# Sheet1.net
KiCad netlist of a schematic drawn in Altium Designer
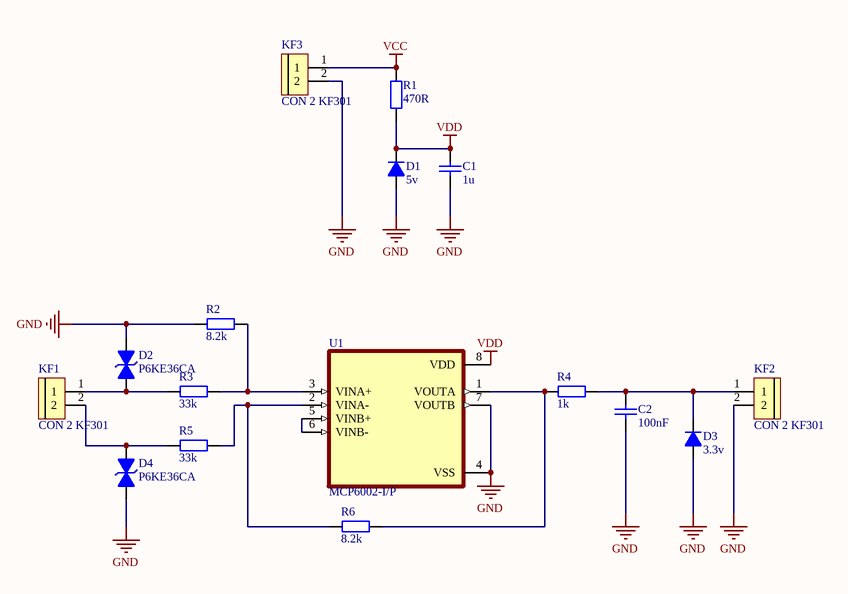
[diagram p0: Sheet1.SchDoc]

(export (version "E")
  (design (tool "Eeschema 10.0.6"))
  (components
    (comp (ref "C1")
      (value "1u")
      (footprint "tu gom")
      (description "Cắm")
      (libsource (lib "Altium_Lib_by_KhueNguyenCreator") (part "Tu gom 15pF 50V"))
    )
    (comp (ref "C2")
      (value "100nF")
      (footprint "tu gom")
      (description "Cắm")
      (libsource (lib "Altium_Lib_by_KhueNguyenCreator") (part "Tu gom 15pF 50V"))
    )
    (comp (ref "D1")
      (value "5v")
      (footprint "DIODE 1A")
      (description "Cắm")
      (libsource (lib "Altium_Lib_by_KhueNguyenCreator") (part "Diode 1N4007"))
    )
    (comp (ref "D2")
      (value "P6KE36CA")
      (footprint "DIODE 1A")
      (description "TVS Diodes P6KE36CA 600W 36V DO-15 (DO-204AC)")
      (libsource (lib "Altium_Lib_by_KhueNguyenCreator") (part "Diode P6KE36CA"))
    )
    (comp (ref "D3")
      (value "3.3v")
      (footprint "DIODE 1A")
      (description "Cắm")
      (libsource (lib "Altium_Lib_by_KhueNguyenCreator") (part "Diode 1N4007"))
    )
    (comp (ref "D4")
      (value "P6KE36CA")
      (footprint "DIODE 1A")
      (description "TVS Diodes P6KE36CA 600W 36V DO-15 (DO-204AC)")
      (libsource (lib "Altium_Lib_by_KhueNguyenCreator") (part "Diode P6KE36CA"))
    )
    (comp (ref "KF1")
      (value "CON 2 KF301")
      (footprint "Con 2 KF301 5.08")
      (description "Cắm")
      (libsource (lib "") (part "CON 2 KF301_1"))
    )
    (comp (ref "KF2")
      (value "CON 2 KF301")
      (footprint "Con 2 KF301 5.08")
      (description "Cắm")
      (libsource (lib "Altium_Lib_by_KhueNguyenCreator") (part "CON 2 KF301"))
    )
    (comp (ref "KF3")
      (value "CON 2 KF301")
      (footprint "Con 2 KF301 5.08")
      (description "Cắm")
      (libsource (lib "") (part "CON 2 KF301_1"))
    )
    (comp (ref "R1")
      (value "470R")
      (footprint "tro vach 1/2w")
      (description "Cắm")
      (libsource (lib "Altium_Lib_by_KhueNguyenCreator") (part "Tro Vach 1/2W 5% 0.22R"))
    )
    (comp (ref "R2")
      (value "8.2k")
      (footprint "tro vach 1/2w")
      (description "Cắm")
      (libsource (lib "Altium_Lib_by_KhueNguyenCreator") (part "Tro Vach 1/2W 5% 0.22R"))
    )
    (comp (ref "R3")
      (value "33k")
      (footprint "tro vach 1/2w")
      (description "Cắm")
      (libsource (lib "Altium_Lib_by_KhueNguyenCreator") (part "Tro Vach 1/2W 5% 0.22R"))
    )
    (comp (ref "R4")
      (value "1k")
      (footprint "tro vach 1/2w")
      (description "Cắm")
      (libsource (lib "Altium_Lib_by_KhueNguyenCreator") (part "Tro Vach 1/2W 5% 0.22R"))
    )
    (comp (ref "R5")
      (value "33k")
      (footprint "tro vach 1/2w")
      (description "Cắm")
      (libsource (lib "Altium_Lib_by_KhueNguyenCreator") (part "Tro Vach 1/2W 5% 0.22R"))
    )
    (comp (ref "R6")
      (value "8.2k")
      (footprint "tro vach 1/2w")
      (description "Cắm")
      (libsource (lib "Altium_Lib_by_KhueNguyenCreator") (part "Tro Vach 1/2W 5% 0.22R"))
    )
    (comp (ref "U1")
      (value "MCP6002-I/P")
      (footprint "DIP787W46P254L927H533Q8")
      (fields (field (name "MF") "Microchip"))
      (libsource (lib "MCP6002-I_P") (part "MCP6002-I/P"))
    )
  )
  (nets
    (net (code "1") (name "GND") (class "Default")
      (node (ref "C1") (pin "2") (pinfunction "2_2") (pintype "passive"))
      (node (ref "C2") (pin "2") (pinfunction "2_2") (pintype "passive"))
      (node (ref "D1") (pin "1") (pinfunction "A_1") (pintype "passive"))
      (node (ref "D2") (pin "1") (pinfunction "A_1") (pintype "passive"))
      (node (ref "D3") (pin "1") (pinfunction "A_1") (pintype "passive"))
      (node (ref "D4") (pin "2") (pinfunction "K_2") (pintype "passive"))
      (node (ref "KF2") (pin "2") (pinfunction "2_2") (pintype "passive"))
      (node (ref "KF3") (pin "2") (pinfunction "2_2") (pintype "passive"))
      (node (ref "R2") (pin "2") (pinfunction "2_2") (pintype "passive"))
      (node (ref "U1") (pin "4") (pinfunction "VSS_4") (pintype "power_in"))
      (node (ref "U1") (pin "7") (pinfunction "VOUTB_7") (pintype "output"))
    )
    (net (code "2") (name "Net-(D2-K)") (class "Default")
      (node (ref "D2") (pin "2") (pinfunction "K_2") (pintype "passive"))
      (node (ref "KF1") (pin "1") (pinfunction "1_1") (pintype "passive"))
      (node (ref "R3") (pin "1") (pinfunction "1_1") (pintype "passive"))
    )
    (net (code "3") (name "Net-(D3-K)") (class "Default")
      (node (ref "C2") (pin "1") (pinfunction "1_1") (pintype "passive"))
      (node (ref "D3") (pin "2") (pinfunction "K_2") (pintype "passive"))
      (node (ref "KF2") (pin "1") (pinfunction "1_1") (pintype "passive"))
      (node (ref "R4") (pin "2") (pinfunction "2_2") (pintype "passive"))
    )
    (net (code "4") (name "Net-(D4-A)") (class "Default")
      (node (ref "D4") (pin "1") (pinfunction "A_1") (pintype "passive"))
      (node (ref "KF1") (pin "2") (pinfunction "2_2") (pintype "passive"))
      (node (ref "R5") (pin "1") (pinfunction "1_1") (pintype "passive"))
    )
    (net (code "5") (name "Net-(U1-VINA+)") (class "Default")
      (node (ref "R2") (pin "1") (pinfunction "1_1") (pintype "passive"))
      (node (ref "R3") (pin "2") (pinfunction "2_2") (pintype "passive"))
      (node (ref "U1") (pin "3") (pinfunction "VINA+_3") (pintype "input"))
    )
    (net (code "6") (name "Net-(U1-VINA-)") (class "Default")
      (node (ref "R5") (pin "2") (pinfunction "2_2") (pintype "passive"))
      (node (ref "R6") (pin "1") (pinfunction "1_1") (pintype "passive"))
      (node (ref "U1") (pin "2") (pinfunction "VINA-_2") (pintype "input"))
    )
    (net (code "7") (name "Net-(U1-VINB+)") (class "Default")
      (node (ref "U1") (pin "5") (pinfunction "VINB+_5") (pintype "input"))
      (node (ref "U1") (pin "6") (pinfunction "VINB-_6") (pintype "input"))
    )
    (net (code "8") (name "Net-(U1-VOUTA)") (class "Default")
      (node (ref "R4") (pin "1") (pinfunction "1_1") (pintype "passive"))
      (node (ref "R6") (pin "2") (pinfunction "2_2") (pintype "passive"))
      (node (ref "U1") (pin "1") (pinfunction "VOUTA_1") (pintype "output"))
    )
    (net (code "9") (name "VCC") (class "Default")
      (node (ref "KF3") (pin "1") (pinfunction "1_1") (pintype "passive"))
      (node (ref "R1") (pin "1") (pinfunction "1_1") (pintype "passive"))
    )
    (net (code "10") (name "VDD") (class "Default")
      (node (ref "C1") (pin "1") (pinfunction "1_1") (pintype "passive"))
      (node (ref "D1") (pin "2") (pinfunction "K_2") (pintype "passive"))
      (node (ref "R1") (pin "2") (pinfunction "2_2") (pintype "passive"))
      (node (ref "U1") (pin "8") (pinfunction "VDD_8") (pintype "power_in"))
    )
  )
)
